# 3_SENSOR.net
KiCad netlist of a schematic drawn in Altium Designer
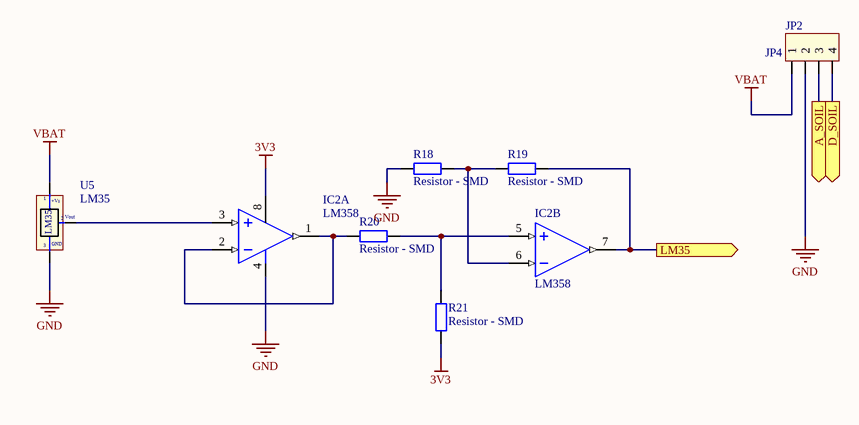
[diagram p0: [3]SENSOR.SchDoc]

(export (version "E")
  (design (tool "Eeschema 10.0.6"))
  (components
    (comp (ref "IC2")
      (value "LM358")
      (footprint "DIP8/W0.3")
      (description "Low-Power Dual Operational Amplifier")
      (libsource (lib "My Library") (part "LM358"))
    )
    (comp (ref "JP2")
      (value "JP4")
      (footprint "CON4")
      (description "Connector 4")
      (libsource (lib "My Library") (part "Con4"))
    )
    (comp (ref "R18")
      (value "Resistor - SMD")
      (footprint "RES_SMD_0805")
      (description "Resistor SMD")
      (fields
        (field (name "MANUFACTURER") "Generic Components")
        (field (name "PUBLISHER") "Altium Hobart Technology Centre")
      )
      (libsource (lib "My Library") (part "Resistor - SMD"))
    )
    (comp (ref "R19")
      (value "Resistor - SMD")
      (footprint "RES_SMD_0805")
      (description "Resistor SMD")
      (fields
        (field (name "MANUFACTURER") "Generic Components")
        (field (name "PUBLISHER") "Altium Hobart Technology Centre")
      )
      (libsource (lib "My Library") (part "Resistor - SMD"))
    )
    (comp (ref "R20")
      (value "Resistor - SMD")
      (footprint "RES_SMD_0805")
      (description "Resistor SMD")
      (fields
        (field (name "MANUFACTURER") "Generic Components")
        (field (name "PUBLISHER") "Altium Hobart Technology Centre")
      )
      (libsource (lib "My Library") (part "Resistor - SMD"))
    )
    (comp (ref "R21")
      (value "Resistor - SMD")
      (footprint "RES_SMD_0805")
      (description "Resistor SMD")
      (fields
        (field (name "MANUFACTURER") "Generic Components")
        (field (name "PUBLISHER") "Altium Hobart Technology Centre")
      )
      (libsource (lib "My Library") (part "Resistor - SMD"))
    )
    (comp (ref "U5")
      (value "LM35")
      (footprint "QTO-92")
      (description "Teminal")
      (libsource (lib "My Library") (part "LM35"))
    )
  )
  (nets
    (net (code "1") (name "/A_SOIL") (class "Default")
      (node (ref "JP2") (pin "3") (pinfunction "3_3") (pintype "passive"))
    )
    (net (code "2") (name "/D_SOIL") (class "Default")
      (node (ref "JP2") (pin "4") (pinfunction "4_4") (pintype "passive"))
    )
    (net (code "3") (name "/LM35") (class "Default")
      (node (ref "IC2") (pin "7") (pinfunction "OUT_7") (pintype "output"))
      (node (ref "R19") (pin "2") (pinfunction "2_2") (pintype "passive"))
    )
    (net (code "4") (name "3V3") (class "Default")
      (node (ref "IC2") (pin "8") (pinfunction "+V_8") (pintype "passive"))
      (node (ref "R21") (pin "2") (pinfunction "2_2") (pintype "passive"))
    )
    (net (code "5") (name "GND") (class "Default")
      (node (ref "IC2") (pin "4") (pinfunction "-V_4") (pintype "passive"))
      (node (ref "JP2") (pin "2") (pinfunction "2_2") (pintype "passive"))
      (node (ref "R18") (pin "1") (pinfunction "1_1") (pintype "passive"))
      (node (ref "U5") (pin "3") (pinfunction "-_3") (pintype "passive"))
    )
    (net (code "6") (name "Net-(IC2A-IN+)") (class "Default")
      (node (ref "IC2") (pin "3") (pinfunction "IN+_3") (pintype "input"))
      (node (ref "U5") (pin "2") (pinfunction "Vout_2") (pintype "passive"))
    )
    (net (code "7") (name "Net-(IC2A-IN-)") (class "Default")
      (node (ref "IC2") (pin "1") (pinfunction "OUT_1") (pintype "output"))
      (node (ref "IC2") (pin "2") (pinfunction "IN-_2") (pintype "input"))
      (node (ref "R20") (pin "2") (pinfunction "2_2") (pintype "passive"))
    )
    (net (code "8") (name "Net-(IC2B-IN+)") (class "Default")
      (node (ref "IC2") (pin "5") (pinfunction "IN+_5") (pintype "input"))
      (node (ref "R20") (pin "1") (pinfunction "1_1") (pintype "passive"))
      (node (ref "R21") (pin "1") (pinfunction "1_1") (pintype "passive"))
    )
    (net (code "9") (name "Net-(IC2B-IN-)") (class "Default")
      (node (ref "IC2") (pin "6") (pinfunction "IN-_6") (pintype "input"))
      (node (ref "R18") (pin "2") (pinfunction "2_2") (pintype "passive"))
      (node (ref "R19") (pin "1") (pinfunction "1_1") (pintype "passive"))
    )
    (net (code "10") (name "VBAT") (class "Default")
      (node (ref "JP2") (pin "1") (pinfunction "1_1") (pintype "passive"))
      (node (ref "U5") (pin "1") (pinfunction "+Vs_1") (pintype "passive"))
    )
  )
)
